# pmod-usb-raw.net
KiCad netlist of a schematic drawn in EAGLE
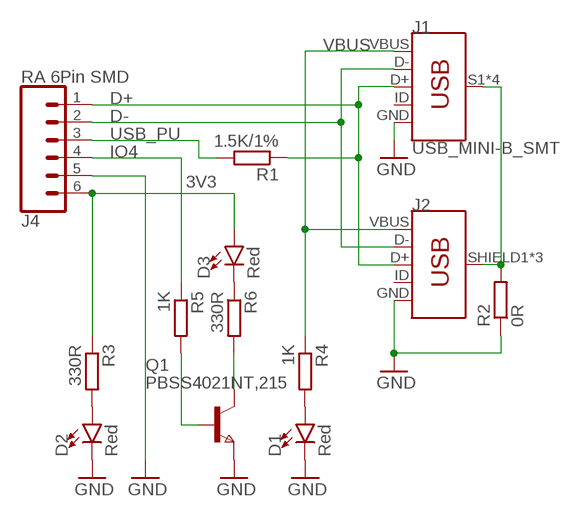
[diagram p0: schematic, sheet 1]

(export (version "E")
  (design (tool "Eeschema 10.0.6"))
  (components
    (comp (ref "D1")
      (value "Red")
      (footprint "eagle-import:LED-0603")
      (libsource (lib "eagle-import") (part "LED-RED0603-SMART"))
    )
    (comp (ref "D2")
      (value "Red")
      (footprint "eagle-import:LED-0603")
      (libsource (lib "eagle-import") (part "LED-RED0603-SMART"))
    )
    (comp (ref "D3")
      (value "Red")
      (footprint "eagle-import:LED-0603")
      (libsource (lib "eagle-import") (part "LED-RED0603-SMART"))
    )
    (comp (ref "J1")
      (value "USB_MINI-B_SMT")
      (footprint "eagle-import:USB-MINIB")
      (libsource (lib "eagle-import") (part "USB_MINI-B_SMT"))
    )
    (comp (ref "J2")
      (value "USB_MICRO-B_FEMALE-SMT")
      (footprint "eagle-import:USB-B-MICRO-SMD")
      (libsource (lib "eagle-import") (part "USB_MICRO-B_FEMALE-SMT"))
    )
    (comp (ref "J4")
      (value "RA 6Pin SMD")
      (footprint "eagle-import:1X06-SMD_RA_MALE")
      (libsource (lib "eagle-import") (part "CONN_06SMD"))
    )
    (comp (ref "Q1")
      (value "PBSS4021NT,215")
      (footprint "eagle-import:SOT23")
      (libsource (lib "eagle-import") (part "PBSS4021NT,215"))
    )
    (comp (ref "R1")
      (value "1.5K/1%")
      (footprint "eagle-import:R0603")
      (libsource (lib "eagle-import") (part "R-EU_R0603"))
    )
    (comp (ref "R2")
      (value "0R")
      (footprint "eagle-import:R0603")
      (libsource (lib "eagle-import") (part "R-EU_R0603"))
    )
    (comp (ref "R3")
      (value "330R")
      (footprint "eagle-import:R0603")
      (libsource (lib "eagle-import") (part "R-EU_R0603"))
    )
    (comp (ref "R4")
      (value "1K")
      (footprint "eagle-import:R0603")
      (libsource (lib "eagle-import") (part "R-EU_R0603"))
    )
    (comp (ref "R5")
      (value "1K")
      (footprint "eagle-import:R0603")
      (libsource (lib "eagle-import") (part "R-EU_R0603"))
    )
    (comp (ref "R6")
      (value "330R")
      (footprint "eagle-import:R0603")
      (libsource (lib "eagle-import") (part "R-EU_R0603"))
    )
  )
  (nets
    (net (code "1") (name "/3V3") (class "Default")
      (node (ref "D3") (pin "A") (pinfunction "A_A") (pintype "passive"))
      (node (ref "J4") (pin "6") (pinfunction "6_6") (pintype "passive"))
      (node (ref "R3") (pin "1") (pinfunction "1_1") (pintype "passive"))
    )
    (net (code "2") (name "/D+") (class "Default")
      (node (ref "J1") (pin "D+") (pinfunction "D+_D+") (pintype "bidirectional"))
      (node (ref "J2") (pin "D+") (pinfunction "D+_D+") (pintype "bidirectional"))
      (node (ref "J4") (pin "1") (pinfunction "1_1") (pintype "passive"))
      (node (ref "R1") (pin "1") (pinfunction "1_1") (pintype "passive"))
    )
    (net (code "3") (name "/D-") (class "Default")
      (node (ref "J1") (pin "D-") (pinfunction "D-_D-") (pintype "bidirectional"))
      (node (ref "J2") (pin "D-") (pinfunction "D-_D-") (pintype "bidirectional"))
      (node (ref "J4") (pin "2") (pinfunction "2_2") (pintype "passive"))
    )
    (net (code "4") (name "/IO4") (class "Default")
      (node (ref "J4") (pin "4") (pinfunction "4_4") (pintype "passive"))
      (node (ref "R5") (pin "1") (pinfunction "1_1") (pintype "passive"))
    )
    (net (code "5") (name "/USB_PU") (class "Default")
      (node (ref "J4") (pin "3") (pinfunction "3_3") (pintype "passive"))
      (node (ref "R1") (pin "2") (pinfunction "2_2") (pintype "passive"))
    )
    (net (code "6") (name "/VBUS") (class "Default")
      (node (ref "J1") (pin "VBUS") (pinfunction "VBUS_VBUS") (pintype "power_in"))
      (node (ref "J2") (pin "VBUS") (pinfunction "VBUS_VBUS") (pintype "power_in"))
      (node (ref "R4") (pin "1") (pinfunction "1_1") (pintype "passive"))
    )
    (net (code "7") (name "GND") (class "Default")
      (node (ref "D1") (pin "C") (pinfunction "C_C") (pintype "passive"))
      (node (ref "D2") (pin "C") (pinfunction "C_C") (pintype "passive"))
      (node (ref "J1") (pin "GND") (pinfunction "GND_GND") (pintype "power_in"))
      (node (ref "J2") (pin "GND") (pinfunction "GND_GND") (pintype "power_in"))
      (node (ref "J4") (pin "5") (pinfunction "5_5") (pintype "passive"))
      (node (ref "Q1") (pin "2") (pinfunction "E_2") (pintype "passive"))
      (node (ref "R2") (pin "1") (pinfunction "1_1") (pintype "passive"))
    )
    (net (code "8") (name "Net-(D1-PadA)") (class "Default")
      (node (ref "D1") (pin "A") (pinfunction "A_A") (pintype "passive"))
      (node (ref "R4") (pin "2") (pinfunction "2_2") (pintype "passive"))
    )
    (net (code "9") (name "Net-(D2-PadA)") (class "Default")
      (node (ref "D2") (pin "A") (pinfunction "A_A") (pintype "passive"))
      (node (ref "R3") (pin "2") (pinfunction "2_2") (pintype "passive"))
    )
    (net (code "10") (name "Net-(D3-PadC)") (class "Default")
      (node (ref "D3") (pin "C") (pinfunction "C_C") (pintype "passive"))
      (node (ref "R6") (pin "1") (pinfunction "1_1") (pintype "passive"))
    )
    (net (code "11") (name "Net-(J1-SHIELD-PadS1)") (class "Default")
      (node (ref "J1") (pin "S1") (pinfunction "SHIELD_S1") (pintype "bidirectional"))
      (node (ref "J1") (pin "S2") (pinfunction "SHIELD_S2") (pintype "bidirectional"))
      (node (ref "J1") (pin "S3") (pinfunction "SHIELD_S3") (pintype "bidirectional"))
      (node (ref "J1") (pin "S4") (pinfunction "SHIELD_S4") (pintype "bidirectional"))
      (node (ref "J2") (pin "SHIELD1") (pinfunction "SHIELD_SHIELD1") (pintype "bidirectional"))
      (node (ref "J2") (pin "SHIELD2") (pinfunction "SHIELD_SHIELD2") (pintype "bidirectional"))
      (node (ref "J2") (pin "SHIELD3") (pinfunction "SHIELD_SHIELD3") (pintype "bidirectional"))
      (node (ref "R2") (pin "2") (pinfunction "2_2") (pintype "passive"))
    )
    (net (code "12") (name "Net-(Q1-B)") (class "Default")
      (node (ref "Q1") (pin "1") (pinfunction "B_1") (pintype "passive"))
      (node (ref "R5") (pin "2") (pinfunction "2_2") (pintype "passive"))
    )
    (net (code "13") (name "Net-(Q1-C)") (class "Default")
      (node (ref "Q1") (pin "3") (pinfunction "C_3") (pintype "passive"))
      (node (ref "R6") (pin "2") (pinfunction "2_2") (pintype "passive"))
    )
    (net (code "14") (name "unconnected-(J1-PadID)") (class "Default")
      (node (ref "J1") (pin "ID") (pinfunction "ID_ID") (pintype "bidirectional"))
    )
    (net (code "15") (name "unconnected-(J2-PadID)") (class "Default")
      (node (ref "J2") (pin "ID") (pinfunction "ID_ID") (pintype "bidirectional"))
    )
  )
)
